# VGA_Blinken.net
KiCad netlist of a schematic drawn in EAGLE
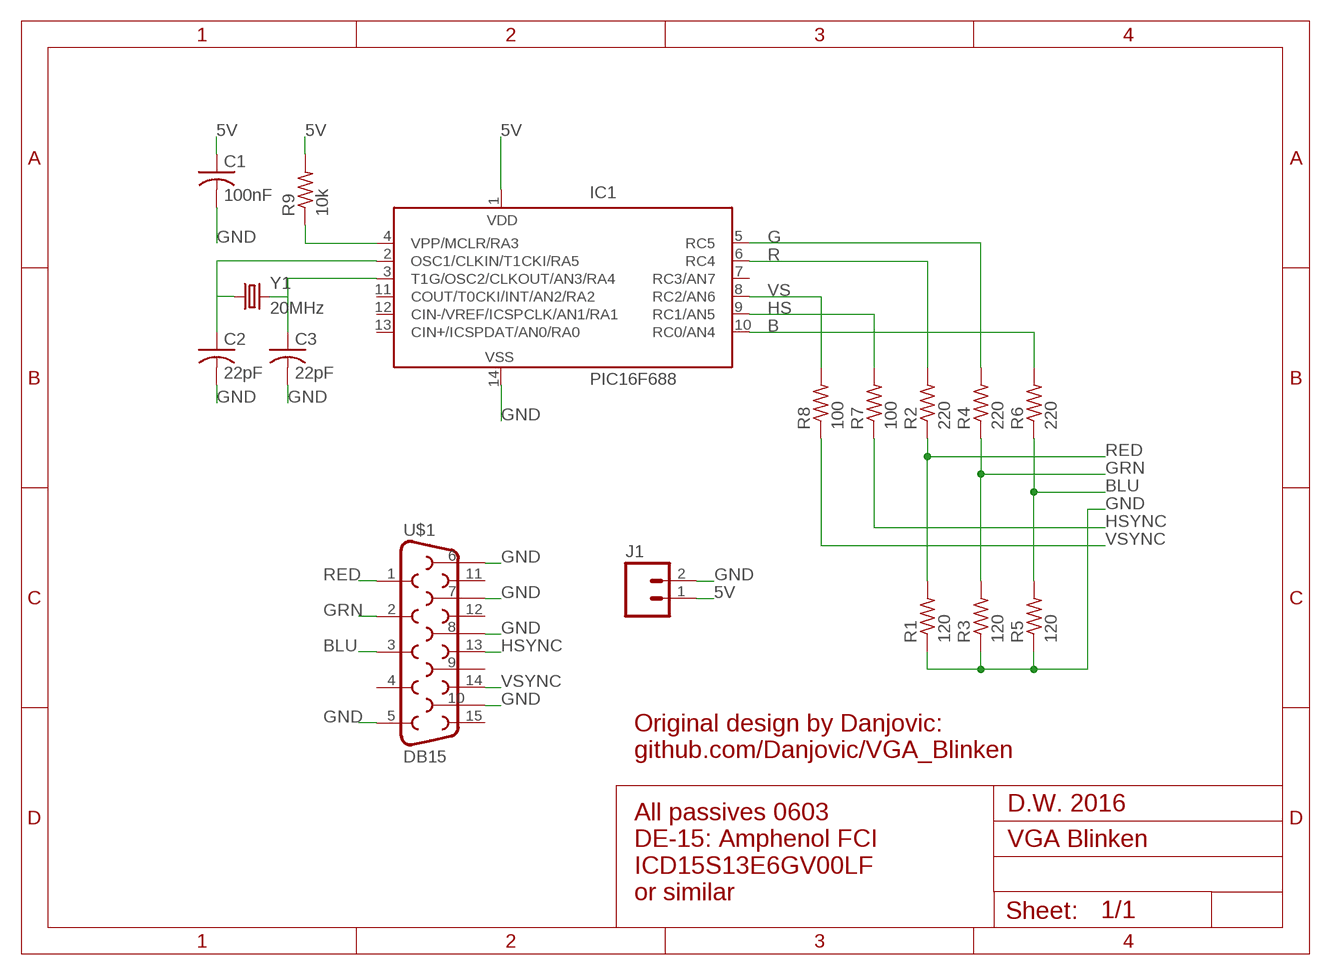
[diagram p0: schematic, sheet 1]

(export (version "E")
  (design (tool "Eeschema 10.0.6"))
  (components
    (comp (ref "C1")
      (value "100nF")
      (footprint "eagle-import:C0603")
      (libsource (lib "eagle-import") (part "C-USC0603"))
    )
    (comp (ref "C2")
      (value "22pF")
      (footprint "eagle-import:C0603")
      (libsource (lib "eagle-import") (part "C-USC0603"))
    )
    (comp (ref "C3")
      (value "22pF")
      (footprint "eagle-import:C0603")
      (libsource (lib "eagle-import") (part "C-USC0603"))
    )
    (comp (ref "IC1")
      (value "PIC16F688")
      (footprint "eagle-import:DIL14")
      (fields (field (name "MF") "MICROCHIP") (field (name "MPN") "PIC16F676-I/P"))
      (libsource (lib "eagle-import") (part "PIC16F676P"))
    )
    (comp (ref "J1")
      (value "M02PTH")
      (footprint "eagle-import:1X02")
      (libsource (lib "eagle-import") (part "M02PTH"))
    )
    (comp (ref "R1")
      (value "120")
      (footprint "eagle-import:R0603")
      (libsource (lib "eagle-import") (part "R-US_R0603"))
    )
    (comp (ref "R2")
      (value "220")
      (footprint "eagle-import:R0603")
      (libsource (lib "eagle-import") (part "R-US_R0603"))
    )
    (comp (ref "R3")
      (value "120")
      (footprint "eagle-import:R0603")
      (libsource (lib "eagle-import") (part "R-US_R0603"))
    )
    (comp (ref "R4")
      (value "220")
      (footprint "eagle-import:R0603")
      (libsource (lib "eagle-import") (part "R-US_R0603"))
    )
    (comp (ref "R5")
      (value "120")
      (footprint "eagle-import:R0603")
      (libsource (lib "eagle-import") (part "R-US_R0603"))
    )
    (comp (ref "R6")
      (value "220")
      (footprint "eagle-import:R0603")
      (libsource (lib "eagle-import") (part "R-US_R0603"))
    )
    (comp (ref "R7")
      (value "100")
      (footprint "eagle-import:R0603")
      (libsource (lib "eagle-import") (part "R-US_R0603"))
    )
    (comp (ref "R8")
      (value "100")
      (footprint "eagle-import:R0603")
      (libsource (lib "eagle-import") (part "R-US_R0603"))
    )
    (comp (ref "R9")
      (value "10k")
      (footprint "eagle-import:R0603")
      (libsource (lib "eagle-import") (part "R-US_R0603"))
    )
    (comp (ref "U$1")
      (value "DB15")
      (footprint "eagle-import:DB15")
      (libsource (lib "eagle-import") (part "DB15"))
    )
    (comp (ref "Y1")
      (value "20MHz")
      (footprint "eagle-import:HC49U-V")
      (libsource (lib "eagle-import") (part "CRYSTALHC49UV"))
    )
  )
  (nets
    (net (code "1") (name "/5V") (class "Default")
      (node (ref "C1") (pin "1") (pinfunction "1_1") (pintype "passive"))
      (node (ref "IC1") (pin "1") (pinfunction "VDD_1") (pintype "power_in"))
      (node (ref "J1") (pin "1") (pinfunction "1_1") (pintype "passive"))
      (node (ref "R9") (pin "2") (pinfunction "2_2") (pintype "passive"))
    )
    (net (code "2") (name "/B") (class "Default")
      (node (ref "IC1") (pin "10") (pinfunction "RC0/AN4_10") (pintype "bidirectional"))
      (node (ref "R6") (pin "2") (pinfunction "2_2") (pintype "passive"))
    )
    (net (code "3") (name "/BLU") (class "Default")
      (node (ref "R5") (pin "2") (pinfunction "2_2") (pintype "passive"))
      (node (ref "R6") (pin "1") (pinfunction "1_1") (pintype "passive"))
      (node (ref "U$1") (pin "3") (pinfunction "3_3") (pintype "passive"))
    )
    (net (code "4") (name "/G") (class "Default")
      (node (ref "IC1") (pin "5") (pinfunction "RC5_5") (pintype "bidirectional"))
      (node (ref "R4") (pin "2") (pinfunction "2_2") (pintype "passive"))
    )
    (net (code "5") (name "/GND") (class "Default")
      (node (ref "C1") (pin "2") (pinfunction "2_2") (pintype "passive"))
      (node (ref "C2") (pin "2") (pinfunction "2_2") (pintype "passive"))
      (node (ref "C3") (pin "2") (pinfunction "2_2") (pintype "passive"))
      (node (ref "IC1") (pin "14") (pinfunction "VSS_14") (pintype "power_in"))
      (node (ref "J1") (pin "2") (pinfunction "2_2") (pintype "passive"))
      (node (ref "R1") (pin "1") (pinfunction "1_1") (pintype "passive"))
      (node (ref "R3") (pin "1") (pinfunction "1_1") (pintype "passive"))
      (node (ref "R5") (pin "1") (pinfunction "1_1") (pintype "passive"))
      (node (ref "U$1") (pin "10") (pinfunction "10_10") (pintype "passive"))
      (node (ref "U$1") (pin "5") (pinfunction "5_5") (pintype "passive"))
      (node (ref "U$1") (pin "6") (pinfunction "6_6") (pintype "passive"))
      (node (ref "U$1") (pin "7") (pinfunction "7_7") (pintype "passive"))
      (node (ref "U$1") (pin "8") (pinfunction "8_8") (pintype "passive"))
    )
    (net (code "6") (name "/GRN") (class "Default")
      (node (ref "R3") (pin "2") (pinfunction "2_2") (pintype "passive"))
      (node (ref "R4") (pin "1") (pinfunction "1_1") (pintype "passive"))
      (node (ref "U$1") (pin "2") (pinfunction "2_2") (pintype "passive"))
    )
    (net (code "7") (name "/HS") (class "Default")
      (node (ref "IC1") (pin "9") (pinfunction "RC1/AN5_9") (pintype "bidirectional"))
      (node (ref "R7") (pin "2") (pinfunction "2_2") (pintype "passive"))
    )
    (net (code "8") (name "/HSYNC") (class "Default")
      (node (ref "R7") (pin "1") (pinfunction "1_1") (pintype "passive"))
      (node (ref "U$1") (pin "13") (pinfunction "13_13") (pintype "passive"))
    )
    (net (code "9") (name "/R") (class "Default")
      (node (ref "IC1") (pin "6") (pinfunction "RC4_6") (pintype "bidirectional"))
      (node (ref "R2") (pin "2") (pinfunction "2_2") (pintype "passive"))
    )
    (net (code "10") (name "/RED") (class "Default")
      (node (ref "R1") (pin "2") (pinfunction "2_2") (pintype "passive"))
      (node (ref "R2") (pin "1") (pinfunction "1_1") (pintype "passive"))
      (node (ref "U$1") (pin "1") (pinfunction "1_1") (pintype "passive"))
    )
    (net (code "11") (name "/VS") (class "Default")
      (node (ref "IC1") (pin "8") (pinfunction "RC2/AN6_8") (pintype "bidirectional"))
      (node (ref "R8") (pin "2") (pinfunction "2_2") (pintype "passive"))
    )
    (net (code "12") (name "/VSYNC") (class "Default")
      (node (ref "R8") (pin "1") (pinfunction "1_1") (pintype "passive"))
      (node (ref "U$1") (pin "14") (pinfunction "14_14") (pintype "passive"))
    )
    (net (code "13") (name "Net-(IC1-OSC1{slash}CLKIN{slash}T1CKI{slash}RA5)") (class "Default")
      (node (ref "C2") (pin "1") (pinfunction "1_1") (pintype "passive"))
      (node (ref "IC1") (pin "2") (pinfunction "OSC1/CLKIN/T1CKI/RA5_2") (pintype "bidirectional"))
      (node (ref "Y1") (pin "1") (pinfunction "1_1") (pintype "passive"))
    )
    (net (code "14") (name "Net-(IC1-T1G{slash}OSC2{slash}CLKOUT{slash}AN3{slash}RA4)") (class "Default")
      (node (ref "C3") (pin "1") (pinfunction "1_1") (pintype "passive"))
      (node (ref "IC1") (pin "3") (pinfunction "T1G/OSC2/CLKOUT/AN3/RA4_3") (pintype "bidirectional"))
      (node (ref "Y1") (pin "2") (pinfunction "2_2") (pintype "passive"))
    )
    (net (code "15") (name "Net-(IC1-VPP{slash}MCLR{slash}RA3)") (class "Default")
      (node (ref "IC1") (pin "4") (pinfunction "VPP/MCLR/RA3_4") (pintype "input"))
      (node (ref "R9") (pin "1") (pinfunction "1_1") (pintype "passive"))
    )
    (net (code "16") (name "unconnected-(IC1-CIN+{slash}ICSPDAT{slash}AN0{slash}RA0-Pad13)") (class "Default")
      (node (ref "IC1") (pin "13") (pinfunction "CIN+/ICSPDAT/AN0/RA0_13") (pintype "bidirectional"))
    )
    (net (code "17") (name "unconnected-(IC1-CIN-{slash}VREF{slash}ICSPCLK{slash}AN1{slash}RA1-Pad12)") (class "Default")
      (node (ref "IC1") (pin "12") (pinfunction "CIN-/VREF/ICSPCLK/AN1/RA1_12") (pintype "bidirectional"))
    )
    (net (code "18") (name "unconnected-(IC1-COUT{slash}T0CKI{slash}INT{slash}AN2{slash}RA2-Pad11)") (class "Default")
      (node (ref "IC1") (pin "11") (pinfunction "COUT/T0CKI/INT/AN2/RA2_11") (pintype "bidirectional"))
    )
    (net (code "19") (name "unconnected-(IC1-RC3{slash}AN7-Pad7)") (class "Default")
      (node (ref "IC1") (pin "7") (pinfunction "RC3/AN7_7") (pintype "bidirectional"))
    )
    (net (code "20") (name "unconnected-(U$1-Pad4)") (class "Default")
      (node (ref "U$1") (pin "4") (pinfunction "4_4") (pintype "passive"))
    )
    (net (code "21") (name "unconnected-(U$1-Pad9)") (class "Default")
      (node (ref "U$1") (pin "9") (pinfunction "9_9") (pintype "passive"))
    )
    (net (code "22") (name "unconnected-(U$1-Pad11)") (class "Default")
      (node (ref "U$1") (pin "11") (pinfunction "11_11") (pintype "passive"))
    )
    (net (code "23") (name "unconnected-(U$1-Pad12)") (class "Default")
      (node (ref "U$1") (pin "12") (pinfunction "12_12") (pintype "passive"))
    )
    (net (code "24") (name "unconnected-(U$1-Pad15)") (class "Default")
      (node (ref "U$1") (pin "15") (pinfunction "15_15") (pintype "passive"))
    )
  )
)
